# cable-adapter-24.net
KiCad netlist of a schematic drawn in EAGLE
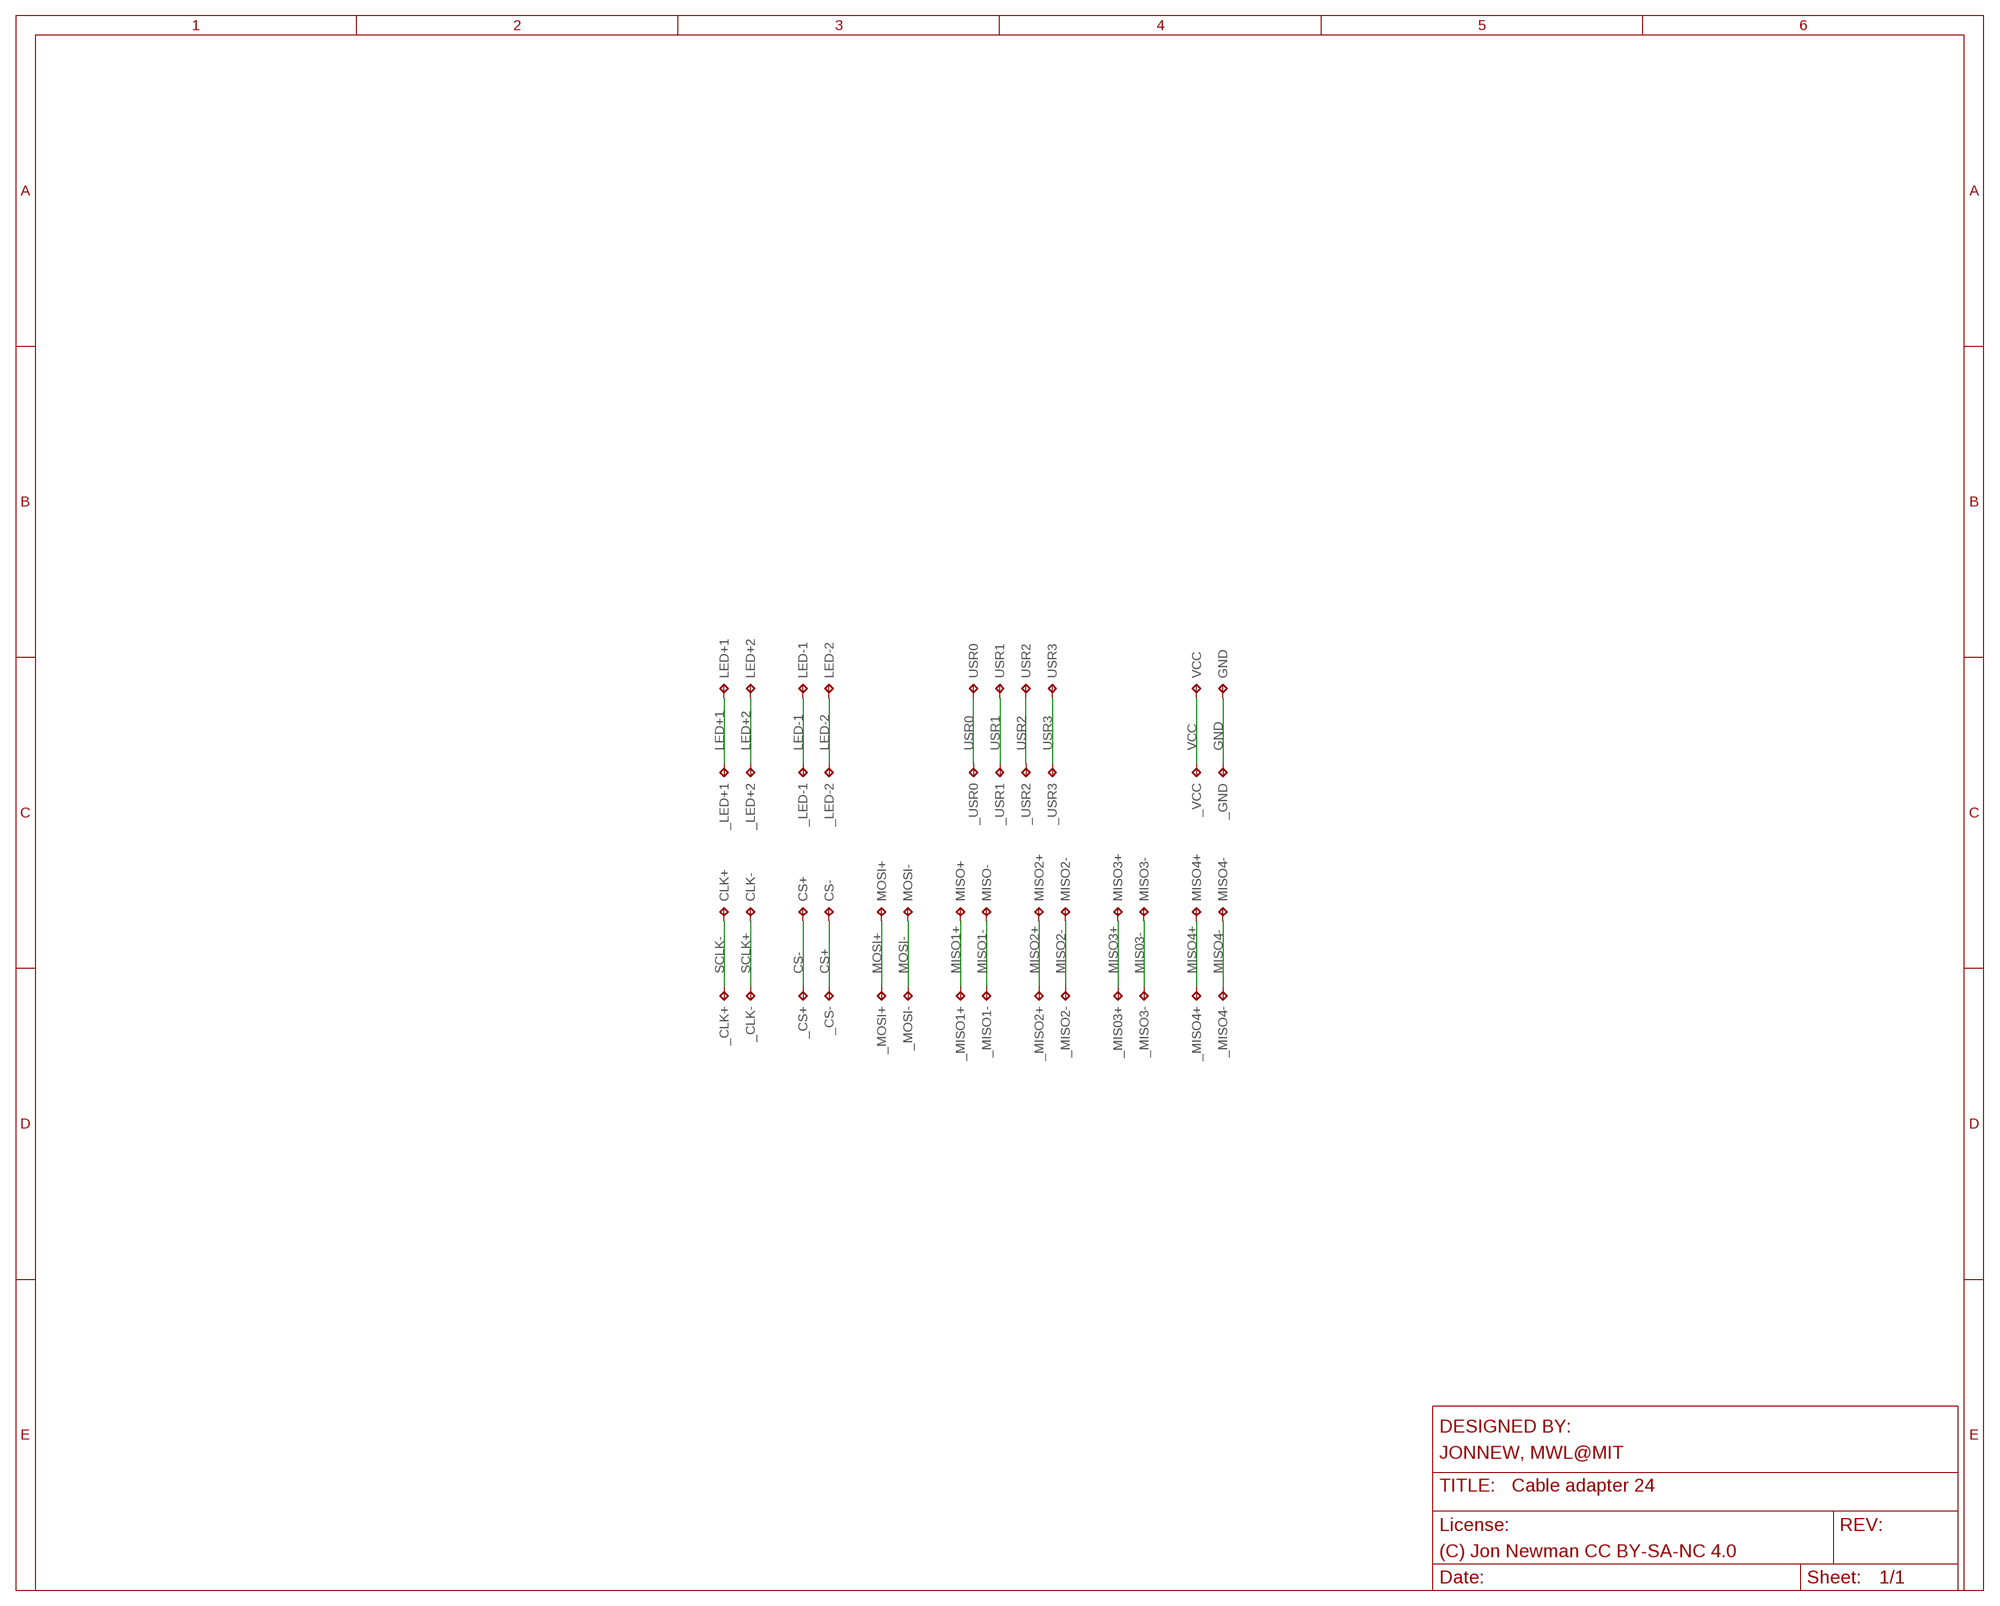
[diagram p0: schematic, sheet 1]

(export (version "E")
  (design (tool "Eeschema 10.0.6"))
  (components
    (comp (ref "CLK+")
      (value "TP_SPI_WIRE+")
      (footprint "eagle-import:SPI_WIRE+")
      (libsource (lib "eagle-import") (part "TP_SPI_WIRE+"))
    )
    (comp (ref "CLK-")
      (value "TP_SPI_WIRE+")
      (footprint "eagle-import:SPI_WIRE+")
      (libsource (lib "eagle-import") (part "TP_SPI_WIRE+"))
    )
    (comp (ref "CS+")
      (value "TP_SPI_WIRE+")
      (footprint "eagle-import:SPI_WIRE+")
      (libsource (lib "eagle-import") (part "TP_SPI_WIRE+"))
    )
    (comp (ref "CS-")
      (value "TP_SPI_WIRE+")
      (footprint "eagle-import:SPI_WIRE+")
      (libsource (lib "eagle-import") (part "TP_SPI_WIRE+"))
    )
    (comp (ref "GND")
      (value "TP_SPI_WIRE+")
      (footprint "eagle-import:SPI_WIRE+")
      (libsource (lib "eagle-import") (part "TP_SPI_WIRE+"))
    )
    (comp (ref "LED+1")
      (value "TP_SPI_WIRE+")
      (footprint "eagle-import:SPI_WIRE+")
      (libsource (lib "eagle-import") (part "TP_SPI_WIRE+"))
    )
    (comp (ref "LED+2")
      (value "TP_SPI_WIRE+")
      (footprint "eagle-import:SPI_WIRE+")
      (libsource (lib "eagle-import") (part "TP_SPI_WIRE+"))
    )
    (comp (ref "LED-1")
      (value "TP_SPI_WIRE+")
      (footprint "eagle-import:SPI_WIRE+")
      (libsource (lib "eagle-import") (part "TP_SPI_WIRE+"))
    )
    (comp (ref "LED-2")
      (value "TP_SPI_WIRE+")
      (footprint "eagle-import:SPI_WIRE+")
      (libsource (lib "eagle-import") (part "TP_SPI_WIRE+"))
    )
    (comp (ref "MISO+")
      (value "TP_SPI_WIRE+")
      (footprint "eagle-import:SPI_WIRE+")
      (libsource (lib "eagle-import") (part "TP_SPI_WIRE+"))
    )
    (comp (ref "MISO-")
      (value "TP_SPI_WIRE+")
      (footprint "eagle-import:SPI_WIRE+")
      (libsource (lib "eagle-import") (part "TP_SPI_WIRE+"))
    )
    (comp (ref "MISO2+")
      (value "TP_SPI_WIRE+")
      (footprint "eagle-import:SPI_WIRE+")
      (libsource (lib "eagle-import") (part "TP_SPI_WIRE+"))
    )
    (comp (ref "MISO2-")
      (value "TP_SPI_WIRE+")
      (footprint "eagle-import:SPI_WIRE+")
      (libsource (lib "eagle-import") (part "TP_SPI_WIRE+"))
    )
    (comp (ref "MISO3+")
      (value "TP_SPI_WIRE+")
      (footprint "eagle-import:SPI_WIRE+")
      (libsource (lib "eagle-import") (part "TP_SPI_WIRE+"))
    )
    (comp (ref "MISO3-")
      (value "TP_SPI_WIRE+")
      (footprint "eagle-import:SPI_WIRE+")
      (libsource (lib "eagle-import") (part "TP_SPI_WIRE+"))
    )
    (comp (ref "MISO4+")
      (value "TP_SPI_WIRE+")
      (footprint "eagle-import:SPI_WIRE+")
      (libsource (lib "eagle-import") (part "TP_SPI_WIRE+"))
    )
    (comp (ref "MISO4-")
      (value "TP_SPI_WIRE+")
      (footprint "eagle-import:SPI_WIRE+")
      (libsource (lib "eagle-import") (part "TP_SPI_WIRE+"))
    )
    (comp (ref "MOSI+")
      (value "TP_SPI_WIRE+")
      (footprint "eagle-import:SPI_WIRE+")
      (libsource (lib "eagle-import") (part "TP_SPI_WIRE+"))
    )
    (comp (ref "MOSI-")
      (value "TP_SPI_WIRE+")
      (footprint "eagle-import:SPI_WIRE+")
      (libsource (lib "eagle-import") (part "TP_SPI_WIRE+"))
    )
    (comp (ref "USR0")
      (value "TP_SPI_WIRE+")
      (footprint "eagle-import:SPI_WIRE+")
      (libsource (lib "eagle-import") (part "TP_SPI_WIRE+"))
    )
    (comp (ref "USR1")
      (value "TP_SPI_WIRE+")
      (footprint "eagle-import:SPI_WIRE+")
      (libsource (lib "eagle-import") (part "TP_SPI_WIRE+"))
    )
    (comp (ref "USR2")
      (value "TP_SPI_WIRE+")
      (footprint "eagle-import:SPI_WIRE+")
      (libsource (lib "eagle-import") (part "TP_SPI_WIRE+"))
    )
    (comp (ref "USR3")
      (value "TP_SPI_WIRE+")
      (footprint "eagle-import:SPI_WIRE+")
      (libsource (lib "eagle-import") (part "TP_SPI_WIRE+"))
    )
    (comp (ref "VCC")
      (value "TP_SPI_WIRE+")
      (footprint "eagle-import:SPI_WIRE+")
      (libsource (lib "eagle-import") (part "TP_SPI_WIRE+"))
    )
    (comp (ref "_CLK+")
      (value "TP_SPI_WIRE+")
      (footprint "eagle-import:SPI_WIRE+")
      (libsource (lib "eagle-import") (part "TP_SPI_WIRE+"))
    )
    (comp (ref "_CLK-")
      (value "TP_SPI_WIRE+")
      (footprint "eagle-import:SPI_WIRE+")
      (libsource (lib "eagle-import") (part "TP_SPI_WIRE+"))
    )
    (comp (ref "_CS+")
      (value "TP_SPI_WIRE+")
      (footprint "eagle-import:SPI_WIRE+")
      (libsource (lib "eagle-import") (part "TP_SPI_WIRE+"))
    )
    (comp (ref "_CS-")
      (value "TP_SPI_WIRE+")
      (footprint "eagle-import:SPI_WIRE+")
      (libsource (lib "eagle-import") (part "TP_SPI_WIRE+"))
    )
    (comp (ref "_GND")
      (value "TP_SPI_WIRE+")
      (footprint "eagle-import:SPI_WIRE+")
      (libsource (lib "eagle-import") (part "TP_SPI_WIRE+"))
    )
    (comp (ref "_LED+1")
      (value "TP_SPI_WIRE+")
      (footprint "eagle-import:SPI_WIRE+")
      (libsource (lib "eagle-import") (part "TP_SPI_WIRE+"))
    )
    (comp (ref "_LED+2")
      (value "TP_SPI_WIRE+")
      (footprint "eagle-import:SPI_WIRE+")
      (libsource (lib "eagle-import") (part "TP_SPI_WIRE+"))
    )
    (comp (ref "_LED-1")
      (value "TP_SPI_WIRE+")
      (footprint "eagle-import:SPI_WIRE+")
      (libsource (lib "eagle-import") (part "TP_SPI_WIRE+"))
    )
    (comp (ref "_LED-2")
      (value "TP_SPI_WIRE+")
      (footprint "eagle-import:SPI_WIRE+")
      (libsource (lib "eagle-import") (part "TP_SPI_WIRE+"))
    )
    (comp (ref "_MIS03+")
      (value "TP_SPI_WIRE+")
      (footprint "eagle-import:SPI_WIRE+")
      (libsource (lib "eagle-import") (part "TP_SPI_WIRE+"))
    )
    (comp (ref "_MISO1+")
      (value "TP_SPI_WIRE+")
      (footprint "eagle-import:SPI_WIRE+")
      (libsource (lib "eagle-import") (part "TP_SPI_WIRE+"))
    )
    (comp (ref "_MISO1-")
      (value "TP_SPI_WIRE+")
      (footprint "eagle-import:SPI_WIRE+")
      (libsource (lib "eagle-import") (part "TP_SPI_WIRE+"))
    )
    (comp (ref "_MISO2+")
      (value "TP_SPI_WIRE+")
      (footprint "eagle-import:SPI_WIRE+")
      (libsource (lib "eagle-import") (part "TP_SPI_WIRE+"))
    )
    (comp (ref "_MISO2-")
      (value "TP_SPI_WIRE+")
      (footprint "eagle-import:SPI_WIRE+")
      (libsource (lib "eagle-import") (part "TP_SPI_WIRE+"))
    )
    (comp (ref "_MISO3-")
      (value "MISO3+")
      (footprint "eagle-import:SPI_WIRE+")
      (libsource (lib "eagle-import") (part "TP_SPI_WIRE+"))
    )
    (comp (ref "_MISO4+")
      (value "TP_SPI_WIRE+")
      (footprint "eagle-import:SPI_WIRE+")
      (libsource (lib "eagle-import") (part "TP_SPI_WIRE+"))
    )
    (comp (ref "_MISO4-")
      (value "TP_SPI_WIRE+")
      (footprint "eagle-import:SPI_WIRE+")
      (libsource (lib "eagle-import") (part "TP_SPI_WIRE+"))
    )
    (comp (ref "_MOSI+")
      (value "TP_SPI_WIRE+")
      (footprint "eagle-import:SPI_WIRE+")
      (libsource (lib "eagle-import") (part "TP_SPI_WIRE+"))
    )
    (comp (ref "_MOSI-")
      (value "TP_SPI_WIRE+")
      (footprint "eagle-import:SPI_WIRE+")
      (libsource (lib "eagle-import") (part "TP_SPI_WIRE+"))
    )
    (comp (ref "_USR0")
      (value "TP_SPI_WIRE+")
      (footprint "eagle-import:SPI_WIRE+")
      (libsource (lib "eagle-import") (part "TP_SPI_WIRE+"))
    )
    (comp (ref "_USR1")
      (value "TP_SPI_WIRE+")
      (footprint "eagle-import:SPI_WIRE+")
      (libsource (lib "eagle-import") (part "TP_SPI_WIRE+"))
    )
    (comp (ref "_USR2")
      (value "TP_SPI_WIRE+")
      (footprint "eagle-import:SPI_WIRE+")
      (libsource (lib "eagle-import") (part "TP_SPI_WIRE+"))
    )
    (comp (ref "_USR3")
      (value "TP_SPI_WIRE+")
      (footprint "eagle-import:SPI_WIRE+")
      (libsource (lib "eagle-import") (part "TP_SPI_WIRE+"))
    )
    (comp (ref "_VCC")
      (value "TP_SPI_WIRE+")
      (footprint "eagle-import:SPI_WIRE+")
      (libsource (lib "eagle-import") (part "TP_SPI_WIRE+"))
    )
  )
  (nets
    (net (code "1") (name "/CS+") (class "Default")
      (node (ref "CS-") (pin "P$1") (pinfunction "TP_P$1") (pintype "input"))
      (node (ref "_CS-") (pin "P$1") (pinfunction "TP_P$1") (pintype "input"))
    )
    (net (code "2") (name "/CS-") (class "Default")
      (node (ref "CS+") (pin "P$1") (pinfunction "TP_P$1") (pintype "input"))
      (node (ref "_CS+") (pin "P$1") (pinfunction "TP_P$1") (pintype "input"))
    )
    (net (code "3") (name "/GND") (class "Default")
      (node (ref "GND") (pin "P$1") (pinfunction "TP_P$1") (pintype "input"))
      (node (ref "_GND") (pin "P$1") (pinfunction "TP_P$1") (pintype "input"))
    )
    (net (code "4") (name "/LED+1") (class "Default")
      (node (ref "LED+1") (pin "P$1") (pinfunction "TP_P$1") (pintype "input"))
      (node (ref "_LED+1") (pin "P$1") (pinfunction "TP_P$1") (pintype "input"))
    )
    (net (code "5") (name "/LED+2") (class "Default")
      (node (ref "LED+2") (pin "P$1") (pinfunction "TP_P$1") (pintype "input"))
      (node (ref "_LED+2") (pin "P$1") (pinfunction "TP_P$1") (pintype "input"))
    )
    (net (code "6") (name "/LED-1") (class "Default")
      (node (ref "LED-1") (pin "P$1") (pinfunction "TP_P$1") (pintype "input"))
      (node (ref "_LED-1") (pin "P$1") (pinfunction "TP_P$1") (pintype "input"))
    )
    (net (code "7") (name "/LED-2") (class "Default")
      (node (ref "LED-2") (pin "P$1") (pinfunction "TP_P$1") (pintype "input"))
      (node (ref "_LED-2") (pin "P$1") (pinfunction "TP_P$1") (pintype "input"))
    )
    (net (code "8") (name "/MIS03-") (class "Default")
      (node (ref "MISO3-") (pin "P$1") (pinfunction "TP_P$1") (pintype "input"))
      (node (ref "_MISO3-") (pin "P$1") (pinfunction "TP_P$1") (pintype "input"))
    )
    (net (code "9") (name "/MISO1+") (class "Default")
      (node (ref "MISO+") (pin "P$1") (pinfunction "TP_P$1") (pintype "input"))
      (node (ref "_MISO1+") (pin "P$1") (pinfunction "TP_P$1") (pintype "input"))
    )
    (net (code "10") (name "/MISO1-") (class "Default")
      (node (ref "MISO-") (pin "P$1") (pinfunction "TP_P$1") (pintype "input"))
      (node (ref "_MISO1-") (pin "P$1") (pinfunction "TP_P$1") (pintype "input"))
    )
    (net (code "11") (name "/MISO2+") (class "Default")
      (node (ref "MISO2+") (pin "P$1") (pinfunction "TP_P$1") (pintype "input"))
      (node (ref "_MISO2+") (pin "P$1") (pinfunction "TP_P$1") (pintype "input"))
    )
    (net (code "12") (name "/MISO2-") (class "Default")
      (node (ref "MISO2-") (pin "P$1") (pinfunction "TP_P$1") (pintype "input"))
      (node (ref "_MISO2-") (pin "P$1") (pinfunction "TP_P$1") (pintype "input"))
    )
    (net (code "13") (name "/MISO3+") (class "Default")
      (node (ref "MISO3+") (pin "P$1") (pinfunction "TP_P$1") (pintype "input"))
      (node (ref "_MIS03+") (pin "P$1") (pinfunction "TP_P$1") (pintype "input"))
    )
    (net (code "14") (name "/MISO4+") (class "Default")
      (node (ref "MISO4+") (pin "P$1") (pinfunction "TP_P$1") (pintype "input"))
      (node (ref "_MISO4+") (pin "P$1") (pinfunction "TP_P$1") (pintype "input"))
    )
    (net (code "15") (name "/MISO4-") (class "Default")
      (node (ref "MISO4-") (pin "P$1") (pinfunction "TP_P$1") (pintype "input"))
      (node (ref "_MISO4-") (pin "P$1") (pinfunction "TP_P$1") (pintype "input"))
    )
    (net (code "16") (name "/MOSI+") (class "Default")
      (node (ref "MOSI+") (pin "P$1") (pinfunction "TP_P$1") (pintype "input"))
      (node (ref "_MOSI+") (pin "P$1") (pinfunction "TP_P$1") (pintype "input"))
    )
    (net (code "17") (name "/MOSI-") (class "Default")
      (node (ref "MOSI-") (pin "P$1") (pinfunction "TP_P$1") (pintype "input"))
      (node (ref "_MOSI-") (pin "P$1") (pinfunction "TP_P$1") (pintype "input"))
    )
    (net (code "18") (name "/SCLK+") (class "Default")
      (node (ref "CLK-") (pin "P$1") (pinfunction "TP_P$1") (pintype "input"))
      (node (ref "_CLK-") (pin "P$1") (pinfunction "TP_P$1") (pintype "input"))
    )
    (net (code "19") (name "/SCLK-") (class "Default")
      (node (ref "CLK+") (pin "P$1") (pinfunction "TP_P$1") (pintype "input"))
      (node (ref "_CLK+") (pin "P$1") (pinfunction "TP_P$1") (pintype "input"))
    )
    (net (code "20") (name "/USR0") (class "Default")
      (node (ref "USR0") (pin "P$1") (pinfunction "TP_P$1") (pintype "input"))
      (node (ref "_USR0") (pin "P$1") (pinfunction "TP_P$1") (pintype "input"))
    )
    (net (code "21") (name "/USR1") (class "Default")
      (node (ref "USR1") (pin "P$1") (pinfunction "TP_P$1") (pintype "input"))
      (node (ref "_USR1") (pin "P$1") (pinfunction "TP_P$1") (pintype "input"))
    )
    (net (code "22") (name "/USR2") (class "Default")
      (node (ref "USR2") (pin "P$1") (pinfunction "TP_P$1") (pintype "input"))
      (node (ref "_USR2") (pin "P$1") (pinfunction "TP_P$1") (pintype "input"))
    )
    (net (code "23") (name "/USR3") (class "Default")
      (node (ref "USR3") (pin "P$1") (pinfunction "TP_P$1") (pintype "input"))
      (node (ref "_USR3") (pin "P$1") (pinfunction "TP_P$1") (pintype "input"))
    )
    (net (code "24") (name "/VCC") (class "Default")
      (node (ref "VCC") (pin "P$1") (pinfunction "TP_P$1") (pintype "input"))
      (node (ref "_VCC") (pin "P$1") (pinfunction "TP_P$1") (pintype "input"))
    )
  )
)
